# DM1092_TopLevel.net
KiCad netlist of a schematic drawn in Altium Designer
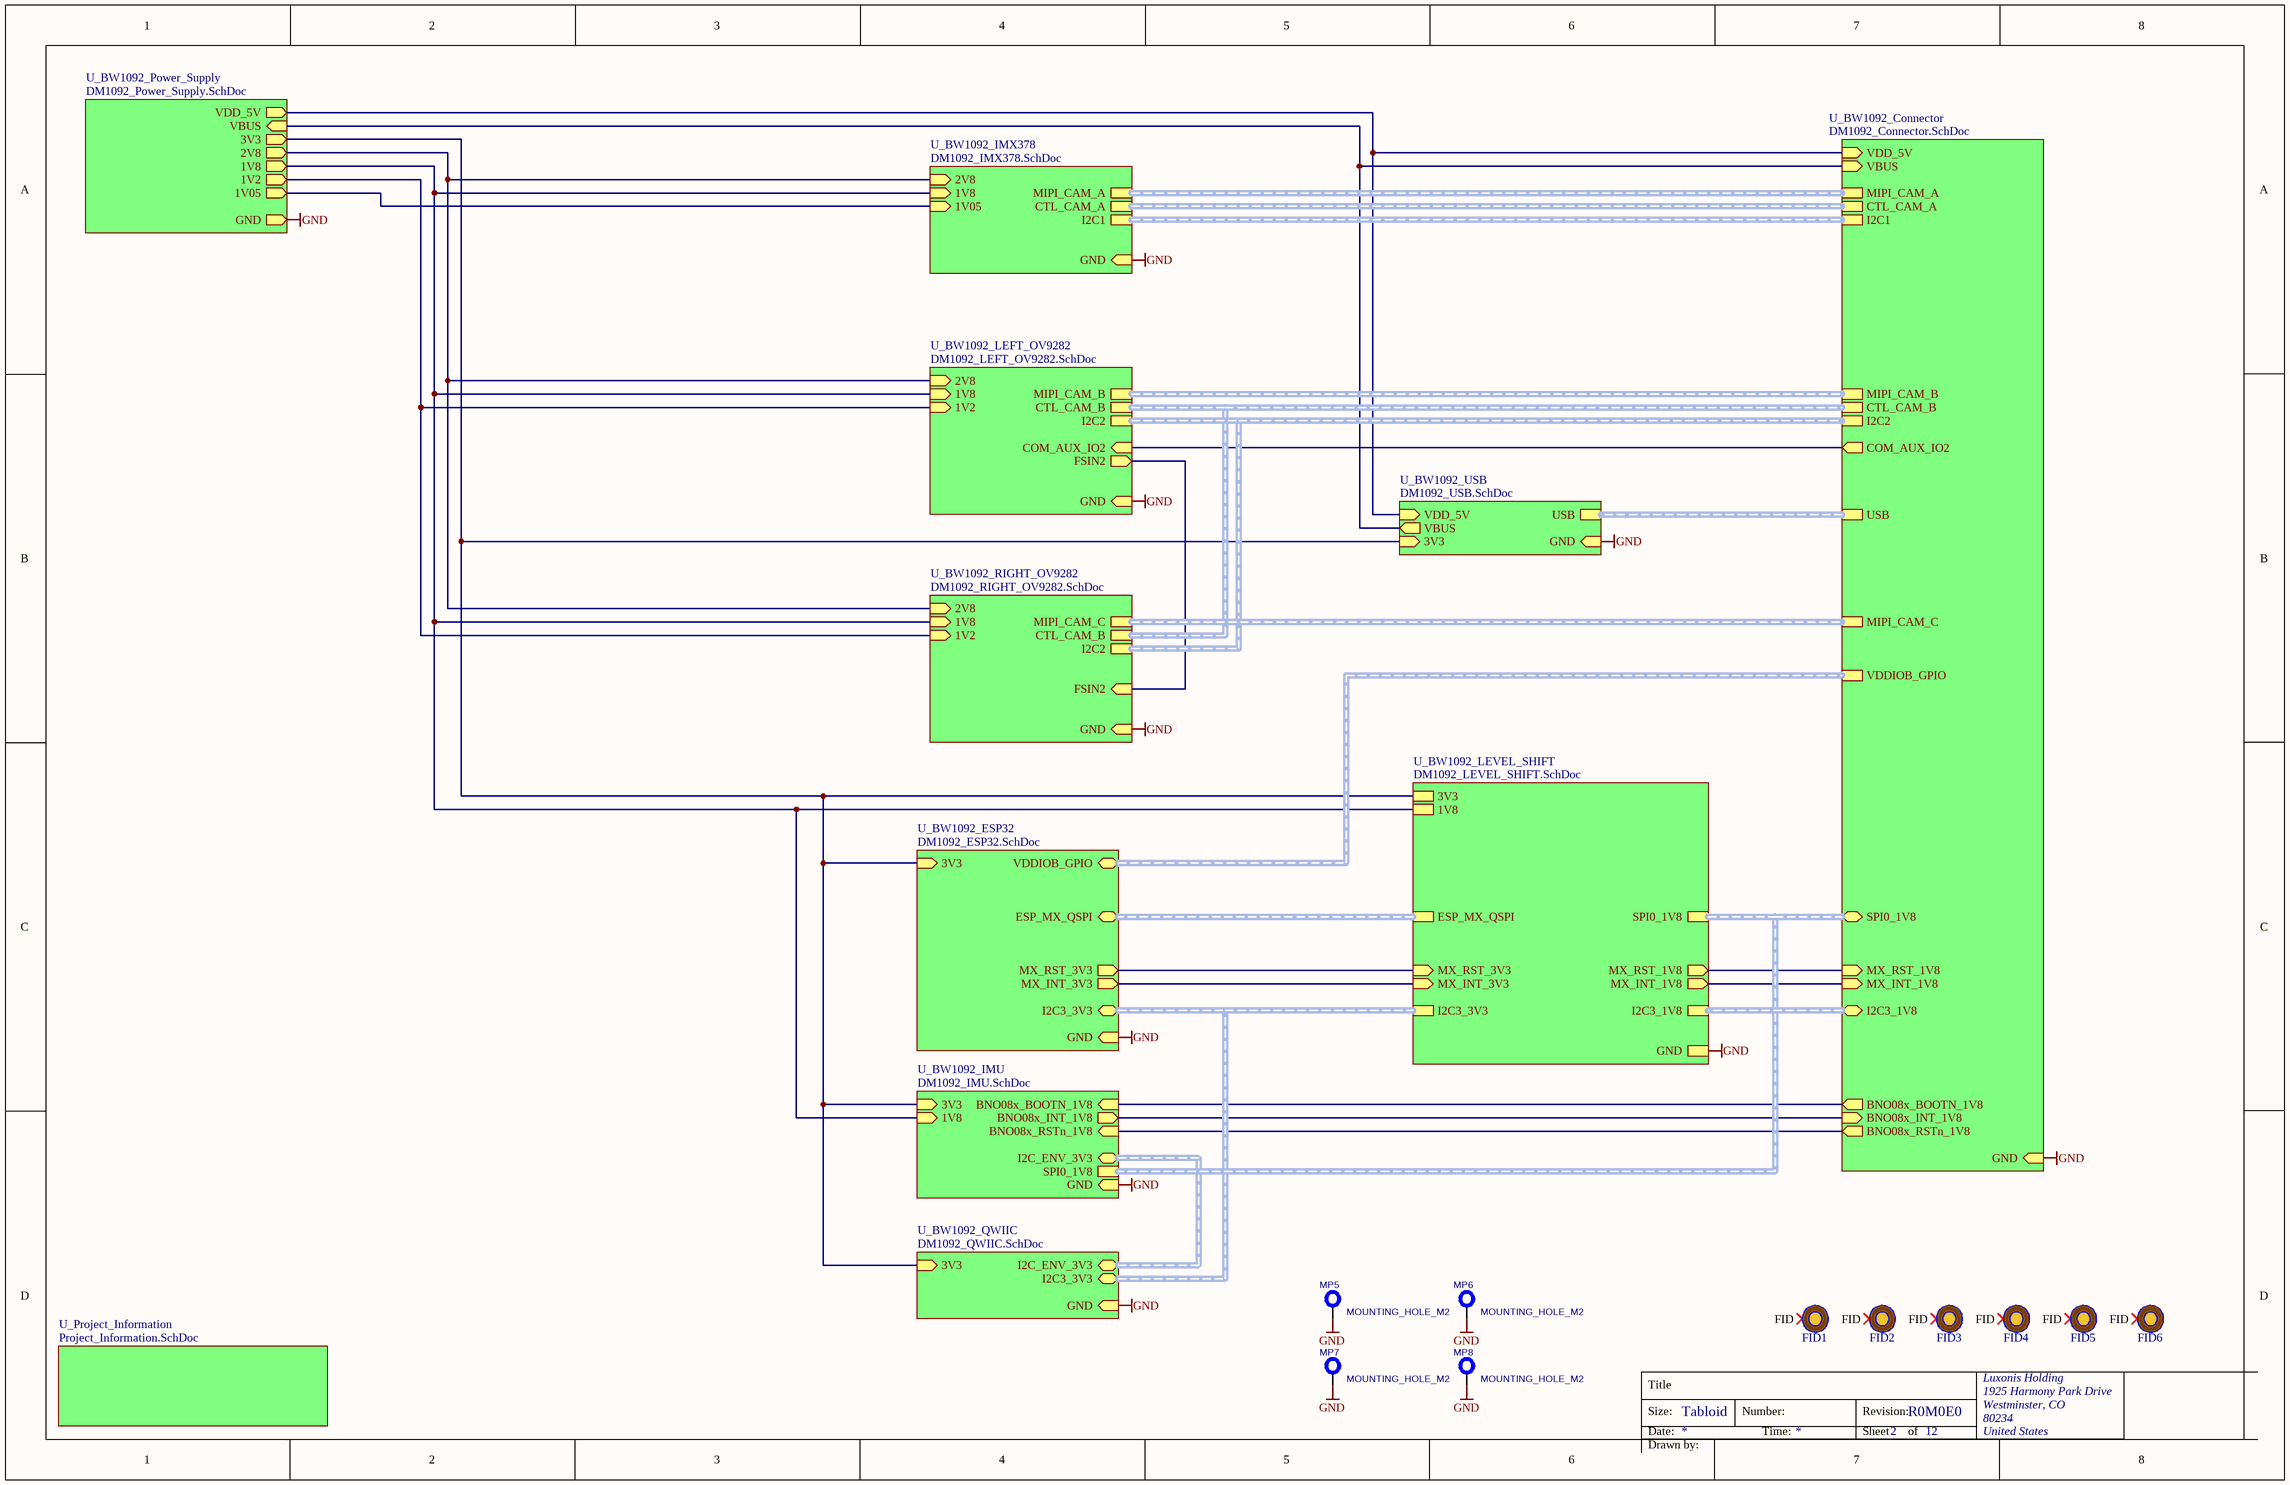
[diagram p0: DM1092_TopLevel.SchDoc]

(export (version "E")
  (design (tool "Eeschema 10.0.6"))
  (components
    (comp (ref "FID1")
      (value "FIDUCIAL_ROUND_1MM")
      (footprint "LuxonisMaster:FIDUCIAL_ROUND_1MM")
      (description "Fiducial with various available footprints")
      (libsource (lib "LuxonisMaster") (part "FIDUCIAL"))
    )
    (comp (ref "FID2")
      (value "FIDUCIAL_ROUND_1MM")
      (footprint "LuxonisMaster:FIDUCIAL_ROUND_1MM")
      (description "Fiducial with various available footprints")
      (libsource (lib "LuxonisMaster") (part "FIDUCIAL"))
    )
    (comp (ref "FID3")
      (value "FIDUCIAL_ROUND_1MM")
      (footprint "LuxonisMaster:FIDUCIAL_ROUND_1MM")
      (description "Fiducial with various available footprints")
      (libsource (lib "LuxonisMaster") (part "FIDUCIAL"))
    )
    (comp (ref "FID4")
      (value "FIDUCIAL_ROUND_1MM")
      (footprint "LuxonisMaster:FIDUCIAL_ROUND_1MM")
      (description "Fiducial with various available footprints")
      (libsource (lib "LuxonisMaster") (part "FIDUCIAL"))
    )
    (comp (ref "FID5")
      (value "FIDUCIAL_ROUND_1MM")
      (footprint "LuxonisMaster:FIDUCIAL_ROUND_1MM")
      (description "Fiducial with various available footprints")
      (libsource (lib "LuxonisMaster") (part "FIDUCIAL"))
    )
    (comp (ref "FID6")
      (value "FIDUCIAL_ROUND_1MM")
      (footprint "LuxonisMaster:FIDUCIAL_ROUND_1MM")
      (description "Fiducial with various available footprints")
      (libsource (lib "LuxonisMaster") (part "FIDUCIAL"))
    )
    (comp (ref "MP5")
      (value "MOUNTING_HOLE_M2")
      (footprint "LuxonisMaster:MOUNTING_HOLE_M2")
      (description "=CurrentFootprint")
      (libsource (lib "LuxonisMaster") (part "MP_Mounting-Holes"))
    )
    (comp (ref "MP6")
      (value "MOUNTING_HOLE_M2")
      (footprint "LuxonisMaster:MOUNTING_HOLE_M2")
      (description "=CurrentFootprint")
      (libsource (lib "LuxonisMaster") (part "MP_Mounting-Holes"))
    )
    (comp (ref "MP7")
      (value "MOUNTING_HOLE_M2")
      (footprint "LuxonisMaster:MOUNTING_HOLE_M2")
      (description "=CurrentFootprint")
      (libsource (lib "LuxonisMaster") (part "MP_Mounting-Holes"))
    )
    (comp (ref "MP8")
      (value "MOUNTING_HOLE_M2")
      (footprint "LuxonisMaster:MOUNTING_HOLE_M2")
      (description "=CurrentFootprint")
      (libsource (lib "LuxonisMaster") (part "MP_Mounting-Holes"))
    )
  )
  (nets
    (net (code "31") (name "GND") (class "Default")
      (node (ref "MP5") (pin "1") (pintype "passive"))
      (node (ref "MP6") (pin "1") (pintype "passive"))
      (node (ref "MP7") (pin "1") (pintype "passive"))
      (node (ref "MP8") (pin "1") (pintype "passive"))
    )
    (net (code "32") (name "unconnected-(FID1-PadFID)") (class "Default")
      (node (ref "FID1") (pin "FID") (pinfunction "FID_FID") (pintype "input+no_connect"))
    )
    (net (code "33") (name "unconnected-(FID2-PadFID)") (class "Default")
      (node (ref "FID2") (pin "FID") (pinfunction "FID_FID") (pintype "input+no_connect"))
    )
    (net (code "34") (name "unconnected-(FID3-PadFID)") (class "Default")
      (node (ref "FID3") (pin "FID") (pinfunction "FID_FID") (pintype "input+no_connect"))
    )
    (net (code "35") (name "unconnected-(FID4-PadFID)") (class "Default")
      (node (ref "FID4") (pin "FID") (pinfunction "FID_FID") (pintype "input+no_connect"))
    )
    (net (code "36") (name "unconnected-(FID5-PadFID)") (class "Default")
      (node (ref "FID5") (pin "FID") (pinfunction "FID_FID") (pintype "input+no_connect"))
    )
    (net (code "37") (name "unconnected-(FID6-PadFID)") (class "Default")
      (node (ref "FID6") (pin "FID") (pinfunction "FID_FID") (pintype "input+no_connect"))
    )
  )
)
